# ssop8_breakout.net
KiCad netlist of a schematic drawn in EAGLE
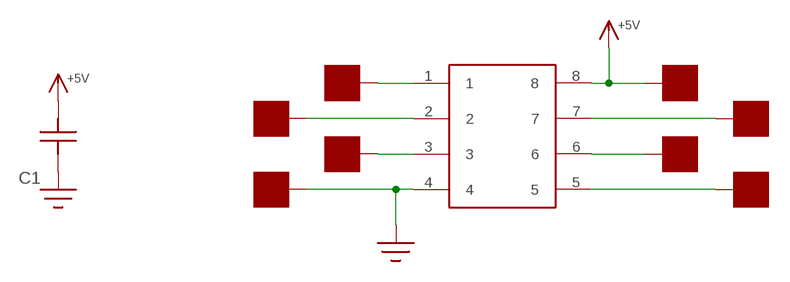
[diagram p0: schematic, sheet 1]

(export (version "E")
  (design (tool "Eeschema 10.0.6"))
  (components
    (comp (ref "C1")
      (value "C0603")
      (footprint "eagle-import:C0603")
      (libsource (lib "eagle-import") (part "C0603"))
    )
    (comp (ref "IC1")
      (value "IC-8PINSSOP8")
      (footprint "eagle-import:SSOP8")
      (libsource (lib "eagle-import") (part "IC-8PINSSOP8"))
    )
    (comp (ref "U$1")
      (value "PAD50MIL")
      (footprint "eagle-import:PAD_50MIL")
      (libsource (lib "eagle-import") (part "PAD50MIL"))
    )
    (comp (ref "U$2")
      (value "PAD50MIL")
      (footprint "eagle-import:PAD_50MIL")
      (libsource (lib "eagle-import") (part "PAD50MIL"))
    )
    (comp (ref "U$3")
      (value "PAD50MIL")
      (footprint "eagle-import:PAD_50MIL")
      (libsource (lib "eagle-import") (part "PAD50MIL"))
    )
    (comp (ref "U$4")
      (value "PAD50MIL")
      (footprint "eagle-import:PAD_50MIL")
      (libsource (lib "eagle-import") (part "PAD50MIL"))
    )
    (comp (ref "U$5")
      (value "PAD50MIL")
      (footprint "eagle-import:PAD_50MIL")
      (libsource (lib "eagle-import") (part "PAD50MIL"))
    )
    (comp (ref "U$6")
      (value "PAD50MIL")
      (footprint "eagle-import:PAD_50MIL")
      (libsource (lib "eagle-import") (part "PAD50MIL"))
    )
    (comp (ref "U$7")
      (value "PAD50MIL")
      (footprint "eagle-import:PAD_50MIL")
      (libsource (lib "eagle-import") (part "PAD50MIL"))
    )
    (comp (ref "U$8")
      (value "PAD50MIL")
      (footprint "eagle-import:PAD_50MIL")
      (libsource (lib "eagle-import") (part "PAD50MIL"))
    )
  )
  (nets
    (net (code "1") (name "+5V") (class "Default")
      (node (ref "C1") (pin "P$1") (pinfunction "P$1_P$1") (pintype "bidirectional"))
      (node (ref "IC1") (pin "8") (pinfunction "8_8") (pintype "bidirectional"))
      (node (ref "U$1") (pin "P$1") (pinfunction "P$1_P$1") (pintype "bidirectional"))
    )
    (net (code "2") (name "GND") (class "Default")
      (node (ref "C1") (pin "P$2") (pinfunction "P$2_P$2") (pintype "bidirectional"))
      (node (ref "IC1") (pin "4") (pinfunction "4_4") (pintype "bidirectional"))
      (node (ref "U$8") (pin "P$1") (pinfunction "P$1_P$1") (pintype "bidirectional"))
    )
    (net (code "3") (name "Net-(IC1-Pad1)") (class "Default")
      (node (ref "IC1") (pin "1") (pinfunction "1_1") (pintype "bidirectional"))
      (node (ref "U$5") (pin "P$1") (pinfunction "P$1_P$1") (pintype "bidirectional"))
    )
    (net (code "4") (name "Net-(IC1-Pad2)") (class "Default")
      (node (ref "IC1") (pin "2") (pinfunction "2_2") (pintype "bidirectional"))
      (node (ref "U$6") (pin "P$1") (pinfunction "P$1_P$1") (pintype "bidirectional"))
    )
    (net (code "5") (name "Net-(IC1-Pad3)") (class "Default")
      (node (ref "IC1") (pin "3") (pinfunction "3_3") (pintype "bidirectional"))
      (node (ref "U$7") (pin "P$1") (pinfunction "P$1_P$1") (pintype "bidirectional"))
    )
    (net (code "6") (name "Net-(IC1-Pad5)") (class "Default")
      (node (ref "IC1") (pin "5") (pinfunction "5_5") (pintype "bidirectional"))
      (node (ref "U$4") (pin "P$1") (pinfunction "P$1_P$1") (pintype "bidirectional"))
    )
    (net (code "7") (name "Net-(IC1-Pad6)") (class "Default")
      (node (ref "IC1") (pin "6") (pinfunction "6_6") (pintype "bidirectional"))
      (node (ref "U$3") (pin "P$1") (pinfunction "P$1_P$1") (pintype "bidirectional"))
    )
    (net (code "8") (name "Net-(IC1-Pad7)") (class "Default")
      (node (ref "IC1") (pin "7") (pinfunction "7_7") (pintype "bidirectional"))
      (node (ref "U$2") (pin "P$1") (pinfunction "P$1_P$1") (pintype "bidirectional"))
    )
  )
)
